# BatterySuperCapBoard.net
KiCad netlist of a schematic drawn in EAGLE
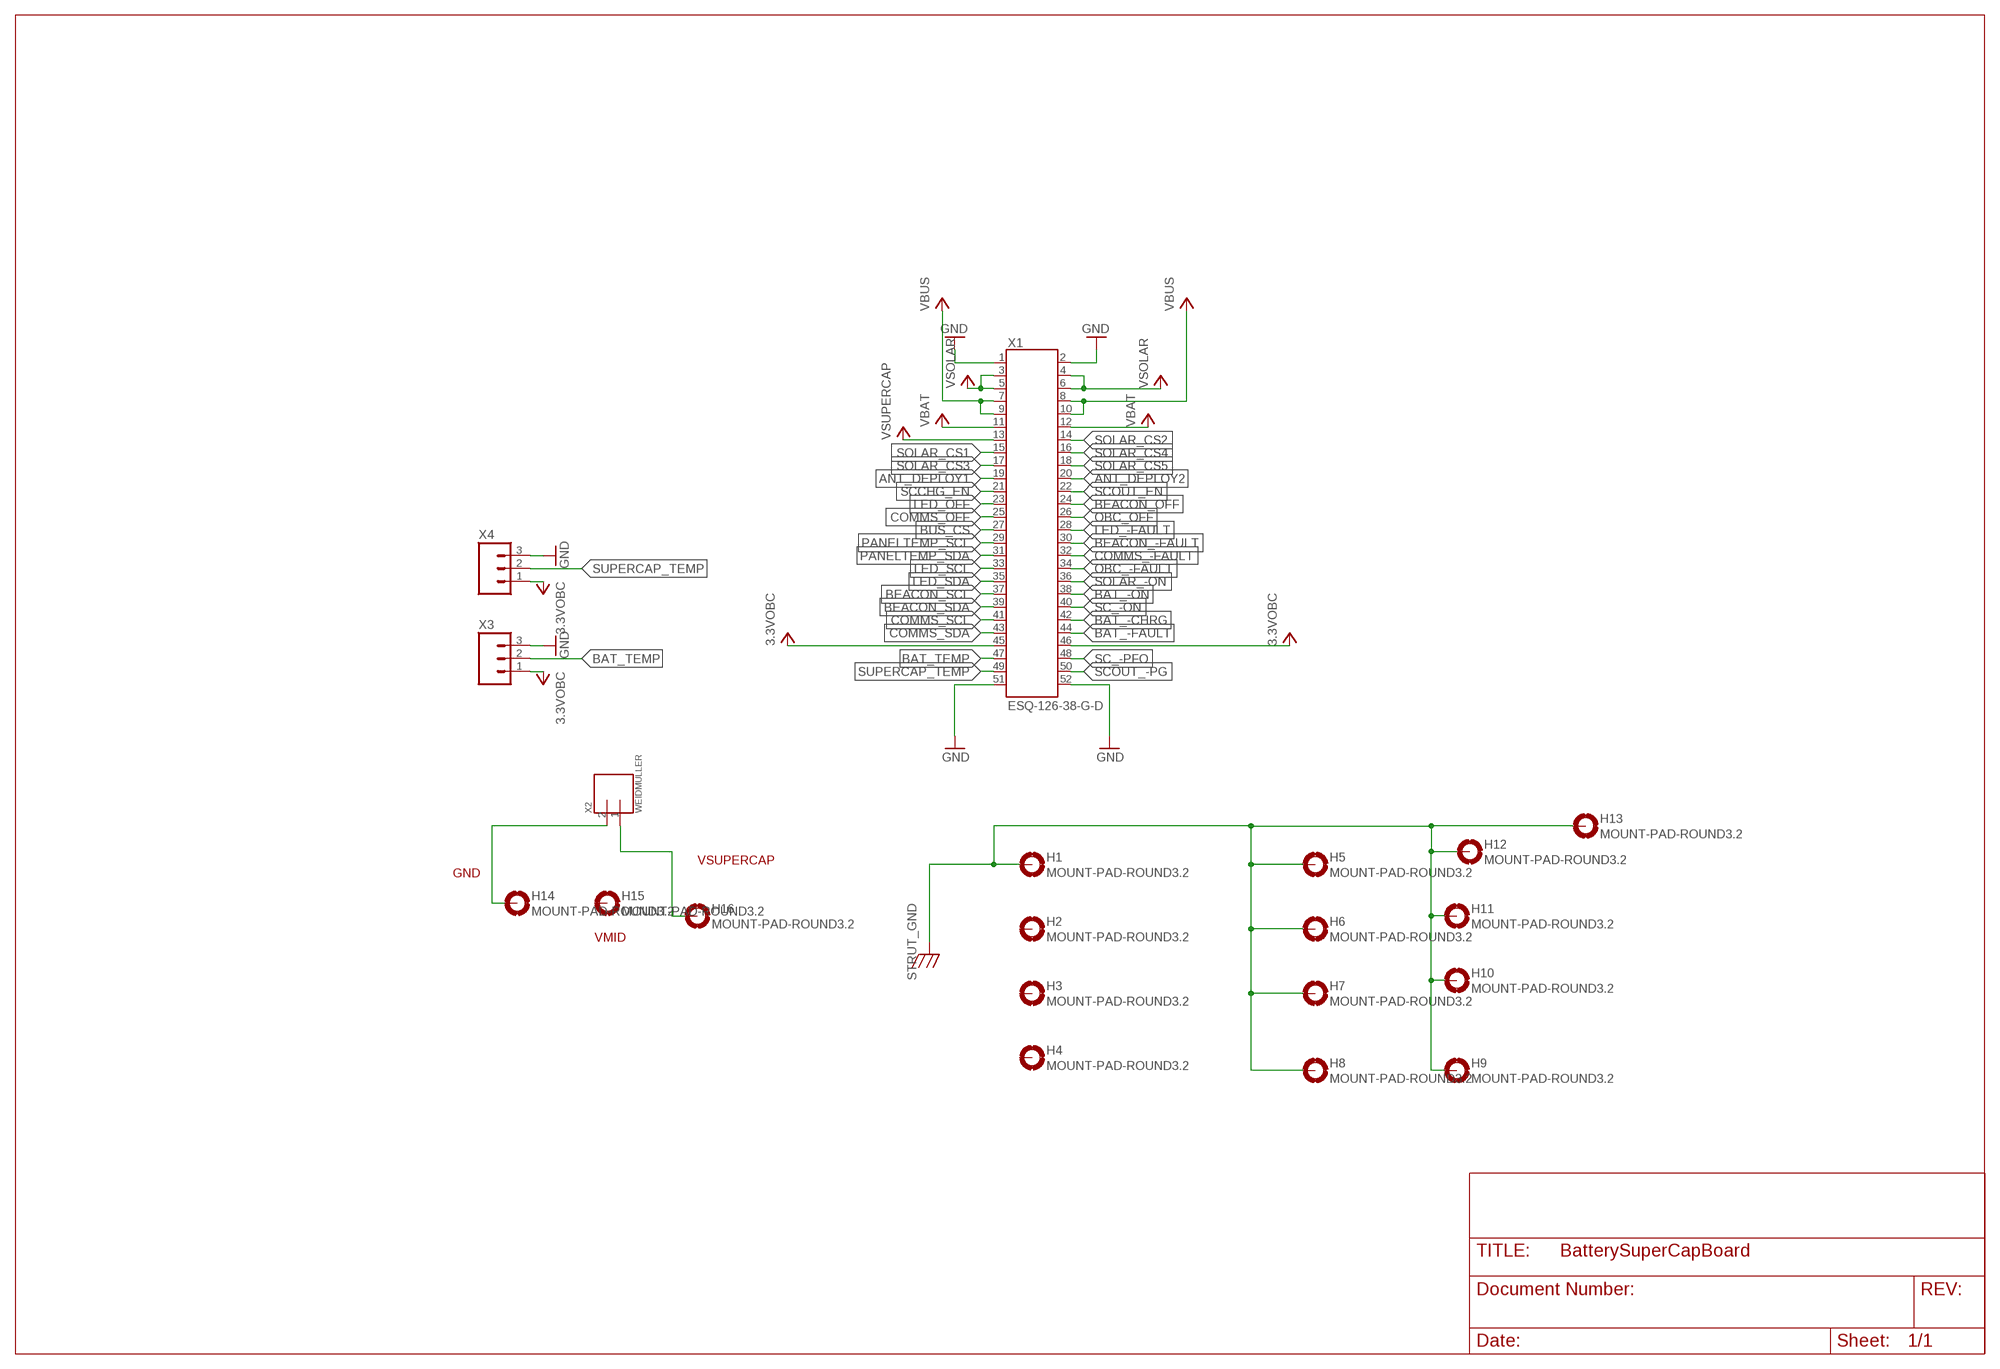
[diagram p0: schematic, sheet 1]

(export (version "E")
  (design (tool "Eeschema 10.0.6"))
  (components
    (comp (ref "H1")
      (value "MOUNT-PAD-ROUND3.2")
      (footprint "eagle-import:3.2-PAD-ROUND")
      (libsource (lib "eagle-import") (part "MOUNT-PAD-ROUND3.2"))
    )
    (comp (ref "H2")
      (value "MOUNT-PAD-ROUND3.2")
      (footprint "eagle-import:3.2-PAD-ROUND")
      (libsource (lib "eagle-import") (part "MOUNT-PAD-ROUND3.2"))
    )
    (comp (ref "H3")
      (value "MOUNT-PAD-ROUND3.2")
      (footprint "eagle-import:3.2-PAD-ROUND")
      (libsource (lib "eagle-import") (part "MOUNT-PAD-ROUND3.2"))
    )
    (comp (ref "H4")
      (value "MOUNT-PAD-ROUND3.2")
      (footprint "eagle-import:3.2-PAD-ROUND")
      (libsource (lib "eagle-import") (part "MOUNT-PAD-ROUND3.2"))
    )
    (comp (ref "H5")
      (value "MOUNT-PAD-ROUND3.2")
      (footprint "eagle-import:3.2-PAD-ROUND")
      (libsource (lib "eagle-import") (part "MOUNT-PAD-ROUND3.2"))
    )
    (comp (ref "H6")
      (value "MOUNT-PAD-ROUND3.2")
      (footprint "eagle-import:3.2-PAD-ROUND")
      (libsource (lib "eagle-import") (part "MOUNT-PAD-ROUND3.2"))
    )
    (comp (ref "H7")
      (value "MOUNT-PAD-ROUND3.2")
      (footprint "eagle-import:3.2-PAD-ROUND")
      (libsource (lib "eagle-import") (part "MOUNT-PAD-ROUND3.2"))
    )
    (comp (ref "H8")
      (value "MOUNT-PAD-ROUND3.2")
      (footprint "eagle-import:3.2-PAD-ROUND")
      (libsource (lib "eagle-import") (part "MOUNT-PAD-ROUND3.2"))
    )
    (comp (ref "H9")
      (value "MOUNT-PAD-ROUND3.2")
      (footprint "eagle-import:3.2-PAD-ROUND")
      (libsource (lib "eagle-import") (part "MOUNT-PAD-ROUND3.2"))
    )
    (comp (ref "H10")
      (value "MOUNT-PAD-ROUND3.2")
      (footprint "eagle-import:3.2-PAD-ROUND")
      (libsource (lib "eagle-import") (part "MOUNT-PAD-ROUND3.2"))
    )
    (comp (ref "H11")
      (value "MOUNT-PAD-ROUND3.2")
      (footprint "eagle-import:3.2-PAD-ROUND")
      (libsource (lib "eagle-import") (part "MOUNT-PAD-ROUND3.2"))
    )
    (comp (ref "H12")
      (value "MOUNT-PAD-ROUND3.2")
      (footprint "eagle-import:3.2-PAD-ROUND")
      (libsource (lib "eagle-import") (part "MOUNT-PAD-ROUND3.2"))
    )
    (comp (ref "H13")
      (value "MOUNT-PAD-ROUND3.2")
      (footprint "eagle-import:3.2-PAD-ROUND")
      (libsource (lib "eagle-import") (part "MOUNT-PAD-ROUND3.2"))
    )
    (comp (ref "H14")
      (value "MOUNT-PAD-ROUND3.2")
      (footprint "eagle-import:3.2-PAD-ROUND")
      (libsource (lib "eagle-import") (part "MOUNT-PAD-ROUND3.2"))
    )
    (comp (ref "H15")
      (value "MOUNT-PAD-ROUND3.2")
      (footprint "eagle-import:3.2-PAD-ROUND")
      (libsource (lib "eagle-import") (part "MOUNT-PAD-ROUND3.2"))
    )
    (comp (ref "H16")
      (value "MOUNT-PAD-ROUND3.2")
      (footprint "eagle-import:3.2-PAD-ROUND")
      (libsource (lib "eagle-import") (part "MOUNT-PAD-ROUND3.2"))
    )
    (comp (ref "X1")
      (value "ESQ-126-38-G-D")
      (footprint "eagle-import:ESQ-126-XX-X-D")
      (libsource (lib "eagle-import") (part "ESQ-126-38-G-D"))
    )
    (comp (ref "X2")
      (value "WEIDMULLER")
      (footprint "eagle-import:WEIDMULLER1760490000")
      (libsource (lib "eagle-import") (part "WEIDMULLER"))
    )
    (comp (ref "X3")
      (value "M03PTH")
      (footprint "eagle-import:1X03")
      (libsource (lib "eagle-import") (part "M03PTH"))
    )
    (comp (ref "X4")
      (value "M03PTH")
      (footprint "eagle-import:1X03")
      (libsource (lib "eagle-import") (part "M03PTH"))
    )
  )
  (nets
    (net (code "1") (name "3.3VOBC") (class "Default")
      (node (ref "X1") (pin "45") (pinfunction "45_45") (pintype "bidirectional"))
      (node (ref "X1") (pin "46") (pinfunction "46_46") (pintype "bidirectional"))
      (node (ref "X3") (pin "1") (pinfunction "1_1") (pintype "passive"))
      (node (ref "X4") (pin "1") (pinfunction "1_1") (pintype "passive"))
    )
    (net (code "2") (name "ANT_DEPLOY1") (class "Default")
      (node (ref "X1") (pin "19") (pinfunction "19_19") (pintype "bidirectional"))
    )
    (net (code "3") (name "ANT_DEPLOY2") (class "Default")
      (node (ref "X1") (pin "20") (pinfunction "20_20") (pintype "bidirectional"))
    )
    (net (code "4") (name "BAT_-CHRG") (class "Default")
      (node (ref "X1") (pin "42") (pinfunction "42_42") (pintype "bidirectional"))
    )
    (net (code "5") (name "BAT_-FAULT") (class "Default")
      (node (ref "X1") (pin "44") (pinfunction "44_44") (pintype "bidirectional"))
    )
    (net (code "6") (name "BAT_-ON") (class "Default")
      (node (ref "X1") (pin "38") (pinfunction "38_38") (pintype "bidirectional"))
    )
    (net (code "7") (name "BAT_TEMP") (class "Default")
      (node (ref "X1") (pin "47") (pinfunction "47_47") (pintype "bidirectional"))
      (node (ref "X3") (pin "2") (pinfunction "2_2") (pintype "passive"))
    )
    (net (code "8") (name "BEACON_-FAULT") (class "Default")
      (node (ref "X1") (pin "30") (pinfunction "30_30") (pintype "bidirectional"))
    )
    (net (code "9") (name "BEACON_OFF") (class "Default")
      (node (ref "X1") (pin "24") (pinfunction "24_24") (pintype "bidirectional"))
    )
    (net (code "10") (name "BEACON_SCL") (class "Default")
      (node (ref "X1") (pin "37") (pinfunction "37_37") (pintype "bidirectional"))
    )
    (net (code "11") (name "BEACON_SDA") (class "Default")
      (node (ref "X1") (pin "39") (pinfunction "39_39") (pintype "bidirectional"))
    )
    (net (code "12") (name "BUS_CS") (class "Default")
      (node (ref "X1") (pin "27") (pinfunction "27_27") (pintype "bidirectional"))
    )
    (net (code "13") (name "COMMS_-FAULT") (class "Default")
      (node (ref "X1") (pin "32") (pinfunction "32_32") (pintype "bidirectional"))
    )
    (net (code "14") (name "COMMS_OFF") (class "Default")
      (node (ref "X1") (pin "25") (pinfunction "25_25") (pintype "bidirectional"))
    )
    (net (code "15") (name "COMMS_SCL") (class "Default")
      (node (ref "X1") (pin "41") (pinfunction "41_41") (pintype "bidirectional"))
    )
    (net (code "16") (name "COMMS_SDA") (class "Default")
      (node (ref "X1") (pin "43") (pinfunction "43_43") (pintype "bidirectional"))
    )
    (net (code "17") (name "GND") (class "Default")
      (node (ref "X1") (pin "1") (pinfunction "1_1") (pintype "bidirectional"))
      (node (ref "X1") (pin "2") (pinfunction "2_2") (pintype "bidirectional"))
      (node (ref "X1") (pin "51") (pinfunction "51_51") (pintype "bidirectional"))
      (node (ref "X1") (pin "52") (pinfunction "52_52") (pintype "bidirectional"))
      (node (ref "X3") (pin "3") (pinfunction "3_3") (pintype "passive"))
      (node (ref "X4") (pin "3") (pinfunction "3_3") (pintype "passive"))
    )
    (net (code "18") (name "LED_-FAULT") (class "Default")
      (node (ref "X1") (pin "28") (pinfunction "28_28") (pintype "bidirectional"))
    )
    (net (code "19") (name "LED_OFF") (class "Default")
      (node (ref "X1") (pin "23") (pinfunction "23_23") (pintype "bidirectional"))
    )
    (net (code "20") (name "LED_SCL") (class "Default")
      (node (ref "X1") (pin "33") (pinfunction "33_33") (pintype "bidirectional"))
    )
    (net (code "21") (name "LED_SDA") (class "Default")
      (node (ref "X1") (pin "35") (pinfunction "35_35") (pintype "bidirectional"))
    )
    (net (code "22") (name "Net-(H14-MOUNT)") (class "Default")
      (node (ref "H14") (pin "B3,2") (pinfunction "MOUNT_B3,2") (pintype "passive"))
      (node (ref "X2") (pin "2") (pinfunction "2_2") (pintype "bidirectional"))
    )
    (net (code "23") (name "Net-(H16-MOUNT)") (class "Default")
      (node (ref "H16") (pin "B3,2") (pinfunction "MOUNT_B3,2") (pintype "passive"))
      (node (ref "X2") (pin "1") (pinfunction "1_1") (pintype "bidirectional"))
    )
    (net (code "24") (name "OBC_-FAULT") (class "Default")
      (node (ref "X1") (pin "34") (pinfunction "34_34") (pintype "bidirectional"))
    )
    (net (code "25") (name "OBC_OFF") (class "Default")
      (node (ref "X1") (pin "26") (pinfunction "26_26") (pintype "bidirectional"))
    )
    (net (code "26") (name "PANELTEMP_SCL") (class "Default")
      (node (ref "X1") (pin "29") (pinfunction "29_29") (pintype "bidirectional"))
    )
    (net (code "27") (name "PANELTEMP_SDA") (class "Default")
      (node (ref "X1") (pin "31") (pinfunction "31_31") (pintype "bidirectional"))
    )
    (net (code "28") (name "SCCHG_EN") (class "Default")
      (node (ref "X1") (pin "21") (pinfunction "21_21") (pintype "bidirectional"))
    )
    (net (code "29") (name "SCOUT_-PG") (class "Default")
      (node (ref "X1") (pin "50") (pinfunction "50_50") (pintype "bidirectional"))
    )
    (net (code "30") (name "SCOUT_EN") (class "Default")
      (node (ref "X1") (pin "22") (pinfunction "22_22") (pintype "bidirectional"))
    )
    (net (code "31") (name "SC_-ON") (class "Default")
      (node (ref "X1") (pin "40") (pinfunction "40_40") (pintype "bidirectional"))
    )
    (net (code "32") (name "SC_-PFO") (class "Default")
      (node (ref "X1") (pin "48") (pinfunction "48_48") (pintype "bidirectional"))
    )
    (net (code "33") (name "SOLAR_-ON") (class "Default")
      (node (ref "X1") (pin "36") (pinfunction "36_36") (pintype "bidirectional"))
    )
    (net (code "34") (name "SOLAR_CS1") (class "Default")
      (node (ref "X1") (pin "15") (pinfunction "15_15") (pintype "bidirectional"))
    )
    (net (code "35") (name "SOLAR_CS2") (class "Default")
      (node (ref "X1") (pin "14") (pinfunction "14_14") (pintype "bidirectional"))
    )
    (net (code "36") (name "SOLAR_CS3") (class "Default")
      (node (ref "X1") (pin "17") (pinfunction "17_17") (pintype "bidirectional"))
    )
    (net (code "37") (name "SOLAR_CS4") (class "Default")
      (node (ref "X1") (pin "16") (pinfunction "16_16") (pintype "bidirectional"))
    )
    (net (code "38") (name "SOLAR_CS5") (class "Default")
      (node (ref "X1") (pin "18") (pinfunction "18_18") (pintype "bidirectional"))
    )
    (net (code "39") (name "STRUT_GND") (class "Default")
      (node (ref "H1") (pin "B3,2") (pinfunction "MOUNT_B3,2") (pintype "passive"))
      (node (ref "H10") (pin "B3,2") (pinfunction "MOUNT_B3,2") (pintype "passive"))
      (node (ref "H11") (pin "B3,2") (pinfunction "MOUNT_B3,2") (pintype "passive"))
      (node (ref "H12") (pin "B3,2") (pinfunction "MOUNT_B3,2") (pintype "passive"))
      (node (ref "H13") (pin "B3,2") (pinfunction "MOUNT_B3,2") (pintype "passive"))
      (node (ref "H5") (pin "B3,2") (pinfunction "MOUNT_B3,2") (pintype "passive"))
      (node (ref "H6") (pin "B3,2") (pinfunction "MOUNT_B3,2") (pintype "passive"))
      (node (ref "H7") (pin "B3,2") (pinfunction "MOUNT_B3,2") (pintype "passive"))
      (node (ref "H8") (pin "B3,2") (pinfunction "MOUNT_B3,2") (pintype "passive"))
      (node (ref "H9") (pin "B3,2") (pinfunction "MOUNT_B3,2") (pintype "passive"))
    )
    (net (code "40") (name "SUPERCAP_TEMP") (class "Default")
      (node (ref "X1") (pin "49") (pinfunction "49_49") (pintype "bidirectional"))
      (node (ref "X4") (pin "2") (pinfunction "2_2") (pintype "passive"))
    )
    (net (code "41") (name "VBAT") (class "Default")
      (node (ref "X1") (pin "11") (pinfunction "11_11") (pintype "bidirectional"))
      (node (ref "X1") (pin "12") (pinfunction "12_12") (pintype "bidirectional"))
    )
    (net (code "42") (name "VBUS") (class "Default")
      (node (ref "X1") (pin "10") (pinfunction "10_10") (pintype "bidirectional"))
      (node (ref "X1") (pin "7") (pinfunction "7_7") (pintype "bidirectional"))
      (node (ref "X1") (pin "8") (pinfunction "8_8") (pintype "bidirectional"))
      (node (ref "X1") (pin "9") (pinfunction "9_9") (pintype "bidirectional"))
    )
    (net (code "43") (name "VSOLAR") (class "Default")
      (node (ref "X1") (pin "3") (pinfunction "3_3") (pintype "bidirectional"))
      (node (ref "X1") (pin "4") (pinfunction "4_4") (pintype "bidirectional"))
      (node (ref "X1") (pin "5") (pinfunction "5_5") (pintype "bidirectional"))
      (node (ref "X1") (pin "6") (pinfunction "6_6") (pintype "bidirectional"))
    )
    (net (code "44") (name "VSUPERCAP") (class "Default")
      (node (ref "X1") (pin "13") (pinfunction "13_13") (pintype "bidirectional"))
    )
    (net (code "45") (name "unconnected-(H2-MOUNT-PadB3,2)") (class "Default")
      (node (ref "H2") (pin "B3,2") (pinfunction "MOUNT_B3,2") (pintype "passive"))
    )
    (net (code "46") (name "unconnected-(H3-MOUNT-PadB3,2)") (class "Default")
      (node (ref "H3") (pin "B3,2") (pinfunction "MOUNT_B3,2") (pintype "passive"))
    )
    (net (code "47") (name "unconnected-(H4-MOUNT-PadB3,2)") (class "Default")
      (node (ref "H4") (pin "B3,2") (pinfunction "MOUNT_B3,2") (pintype "passive"))
    )
    (net (code "48") (name "unconnected-(H15-MOUNT-PadB3,2)") (class "Default")
      (node (ref "H15") (pin "B3,2") (pinfunction "MOUNT_B3,2") (pintype "passive"))
    )
  )
)
